# M5_Stick_DCC_Interface_2020-05-23_20-41-.net
KiCad netlist of a schematic drawn in EasyEDA
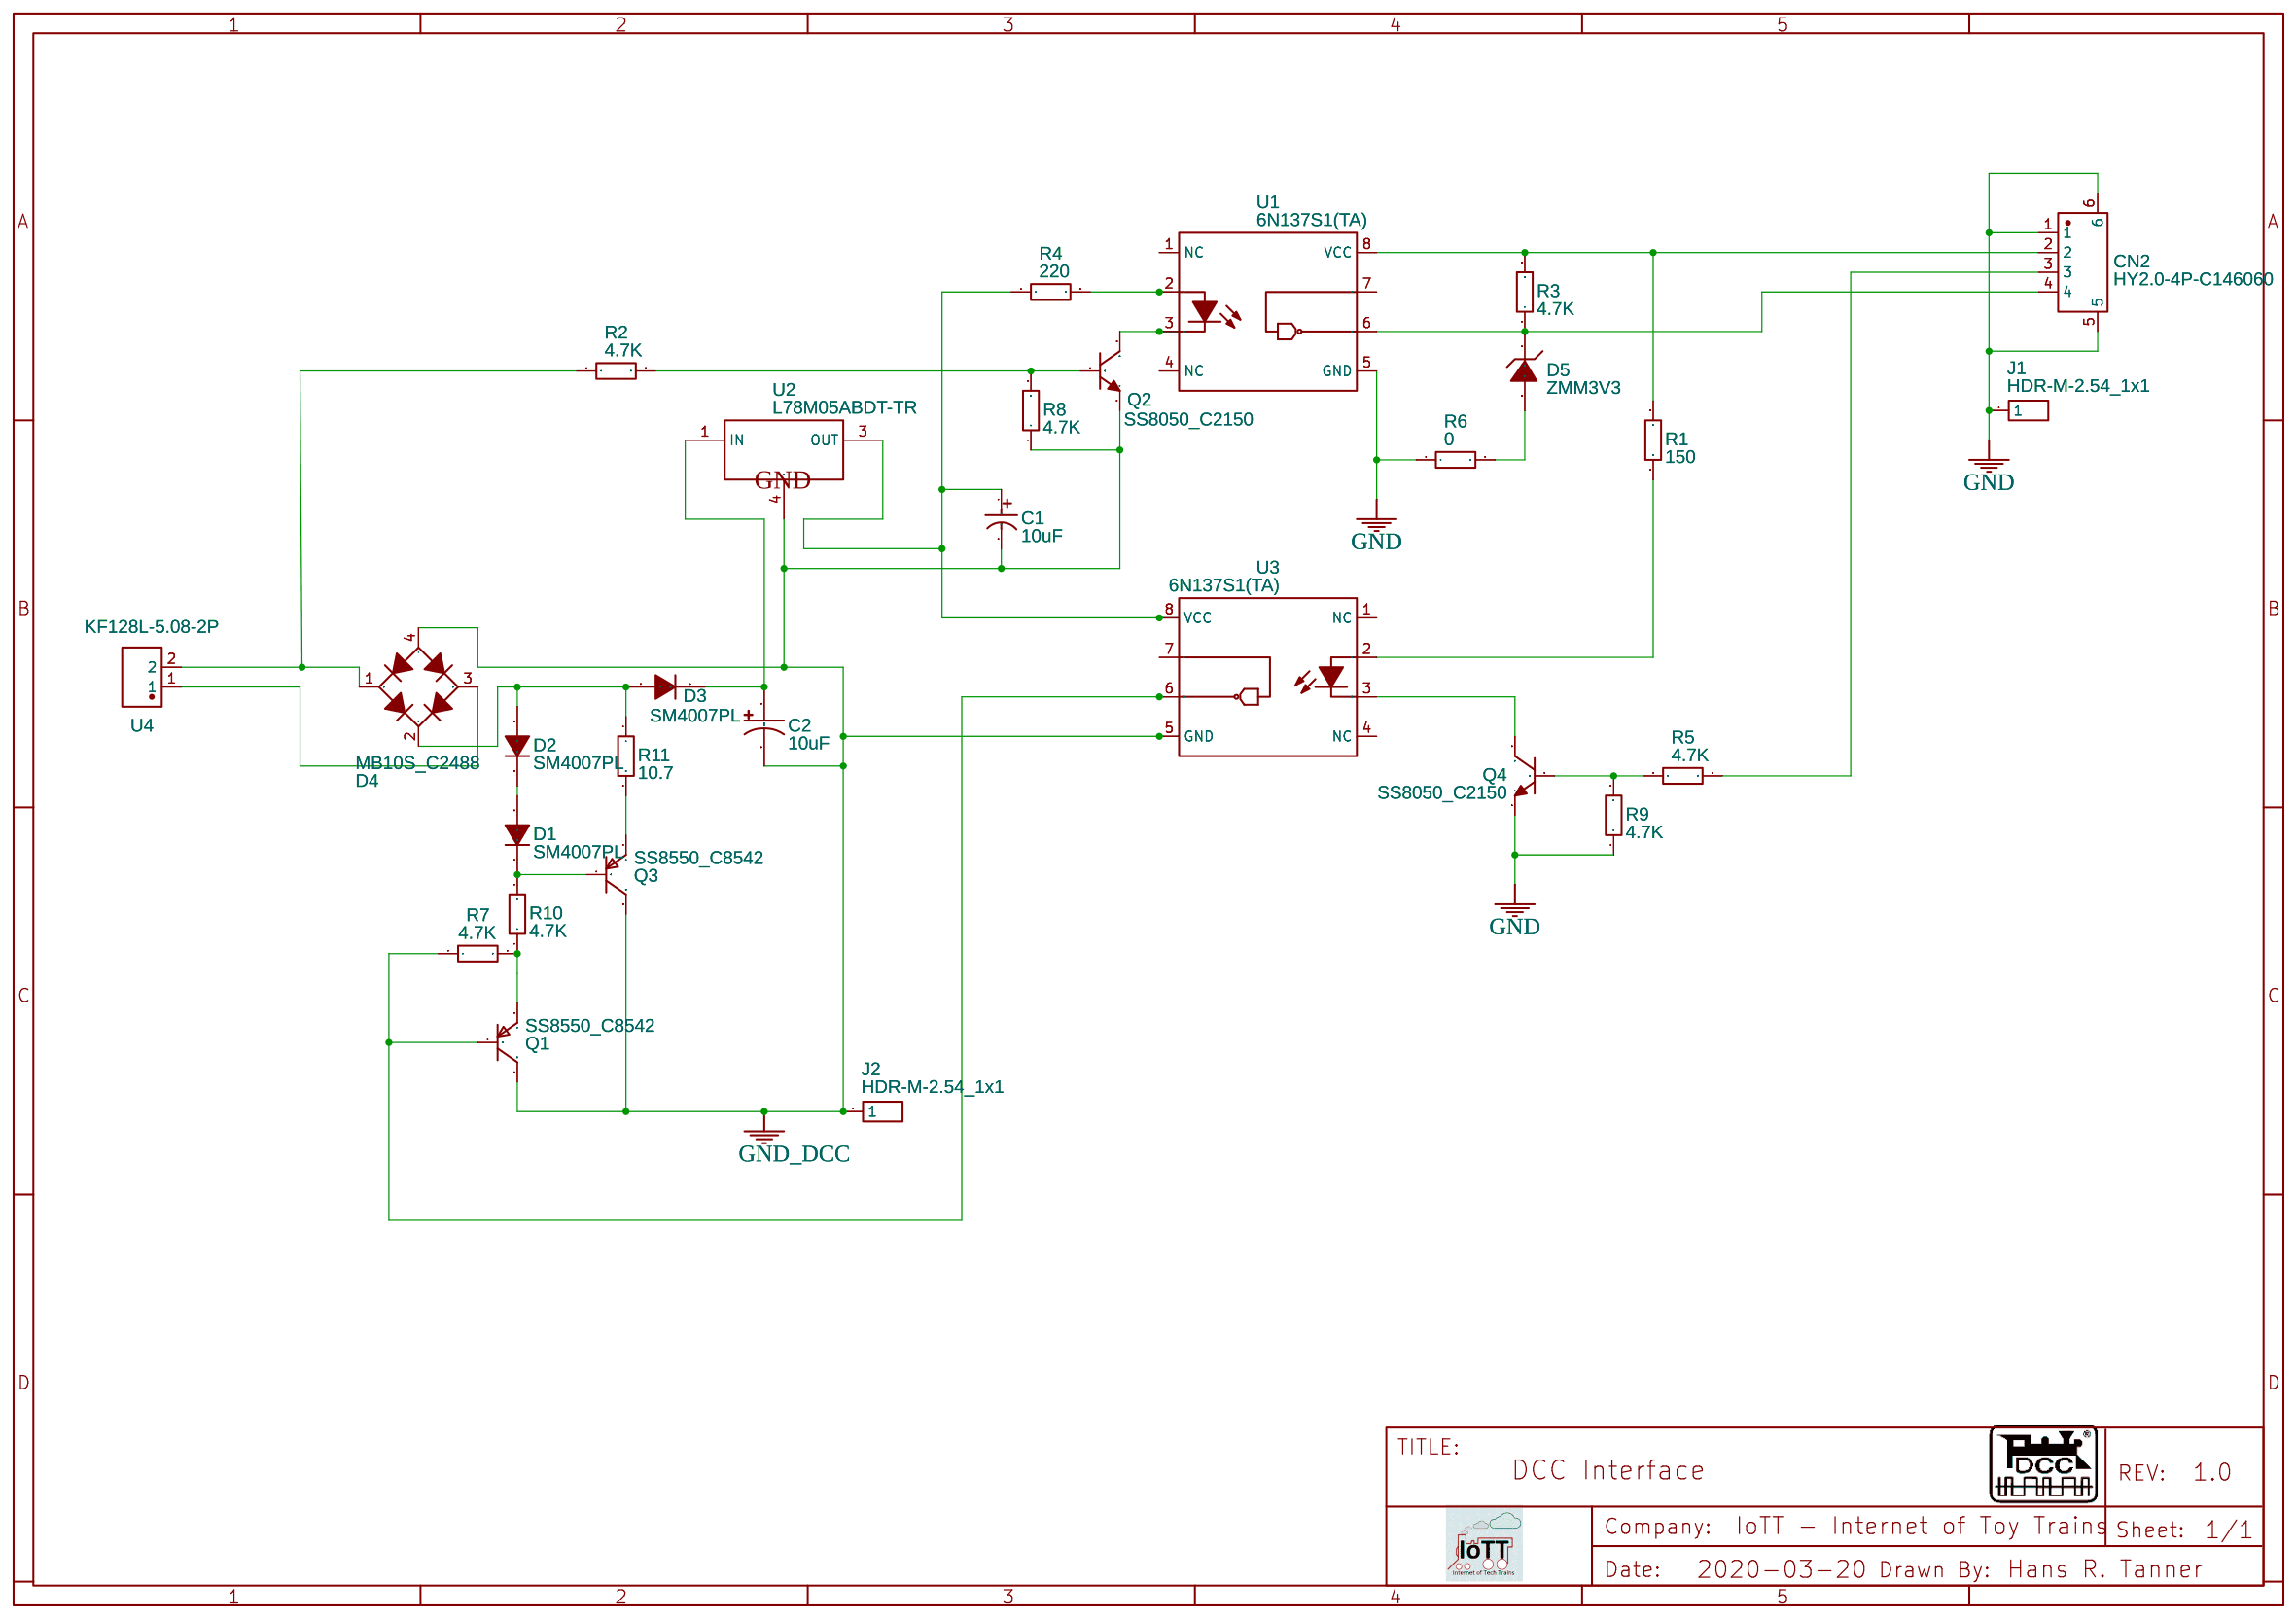
[diagram p0: schematic sheet]

(export (version "E")
  (design (tool "Eeschema 10.0.6"))
  (components
    (comp (ref "C1")
      (value "10uF")
      (fields
        (field (name "BOM_Manufacturer Part") "VE-100M1ETR-0405")
        (field (name "BOM_Supplier Part") "C134721")
      )
      (libsource (lib "") (part "VE-100M1ETR-0405"))
    )
    (comp (ref "C2")
      (value "10uF")
      (fields
        (field (name "BOM_Manufacturer Part") "VE-100M1H0505-TRO")
        (field (name "BOM_Supplier Part") "C249452")
      )
      (libsource (lib "") (part "VE-100M1H0505-TRO"))
    )
    (comp (ref "CN2")
      (value "HY2.0-4P-C146060")
      (fields (field (name "BOM_Supplier Part") "C146060"))
      (libsource (lib "") (part "HY2.0-4P-C146060"))
    )
    (comp (ref "D1")
      (value "SM4007PL")
      (fields (field (name "BOM_Supplier Part") "C64898"))
      (libsource (lib "") (part "SM4007PL"))
    )
    (comp (ref "D2")
      (value "SM4007PL")
      (fields (field (name "BOM_Supplier Part") "C64898"))
      (libsource (lib "") (part "SM4007PL"))
    )
    (comp (ref "D3")
      (value "SM4007PL")
      (fields (field (name "BOM_Supplier Part") "C64898"))
      (libsource (lib "") (part "SM4007PL_1"))
    )
    (comp (ref "D4")
      (value "MB10S_C2488")
      (fields (field (name "BOM_Manufacturer Part") "MB10S") (field (name "BOM_Supplier Part") "C2488"))
      (libsource (lib "") (part "MB10S_C2488"))
    )
    (comp (ref "D5")
      (value "ZMM3V3")
      (fields (field (name "BOM_Supplier Part") "C8056"))
      (libsource (lib "") (part "ZMM3V3"))
    )
    (comp (ref "J1")
      (value "HDR-M-2.54_1x1")
      (fields (field (name "BOM_Supplier Part") "C81276"))
      (libsource (lib "") (part "HDR-M-2.54_1x1"))
    )
    (comp (ref "J2")
      (value "HDR-M-2.54_1x1")
      (fields (field (name "BOM_Supplier Part") "C81276"))
      (libsource (lib "") (part "HDR-M-2.54_1x1"))
    )
    (comp (ref "Q1")
      (value "SS8550_C8542")
      (fields (field (name "BOM_Manufacturer Part") "SS8550") (field (name "BOM_Supplier Part") "C8542"))
      (libsource (lib "") (part "SS8550_C8542"))
    )
    (comp (ref "Q2")
      (value "SS8050_C2150")
      (fields (field (name "BOM_Manufacturer Part") "SS8050") (field (name "BOM_Supplier Part") "C2150"))
      (libsource (lib "") (part "SS8050_C2150"))
    )
    (comp (ref "Q3")
      (value "SS8550_C8542")
      (fields (field (name "BOM_Manufacturer Part") "SS8550") (field (name "BOM_Supplier Part") "C8542"))
      (libsource (lib "") (part "SS8550_C8542"))
    )
    (comp (ref "Q4")
      (value "SS8050_C2150")
      (fields (field (name "BOM_Manufacturer Part") "SS8050") (field (name "BOM_Supplier Part") "C2150"))
      (libsource (lib "") (part "SS8050_C2150_1"))
    )
    (comp (ref "R1")
      (value "150")
      (fields
        (field (name "BOM_Manufacturer Part") "0603WAF1500T5E")
        (field (name "BOM_Supplier Part") "C22808")
      )
      (libsource (lib "") (part "0603WAF1500T5E"))
    )
    (comp (ref "R2")
      (value "4.7K")
      (fields
        (field (name "BOM_Manufacturer Part") "0603WAF4701T5E")
        (field (name "BOM_Supplier Part") "C23162")
      )
      (libsource (lib "") (part "0603WAF4701T5E"))
    )
    (comp (ref "R3")
      (value "4.7K")
      (fields
        (field (name "BOM_Manufacturer Part") "0603WAF4701T5E")
        (field (name "BOM_Supplier Part") "C23162")
      )
      (libsource (lib "") (part "0603WAF1001T5E"))
    )
    (comp (ref "R4")
      (value "220")
      (fields
        (field (name "BOM_Manufacturer Part") "0603WAF2200T5E")
        (field (name "BOM_Supplier Part") "C22962")
      )
      (libsource (lib "") (part "0603WAF1500T5E_1"))
    )
    (comp (ref "R5")
      (value "4.7K")
      (fields
        (field (name "BOM_Manufacturer Part") "0603WAF4701T5E")
        (field (name "BOM_Supplier Part") "C23162")
      )
      (libsource (lib "") (part "0603WAF4701T5E"))
    )
    (comp (ref "R6")
      (value "0")
      (fields
        (field (name "BOM_Manufacturer Part") "0402WGF0000TCE")
        (field (name "BOM_Supplier Part") "C17168")
      )
      (libsource (lib "") (part "0402WGF0000TCE"))
    )
    (comp (ref "R7")
      (value "4.7K")
      (fields
        (field (name "BOM_Manufacturer Part") "0603WAF4701T5E")
        (field (name "BOM_Supplier Part") "C23162")
      )
      (libsource (lib "") (part "0603WAF4701T5E"))
    )
    (comp (ref "R8")
      (value "4.7K")
      (fields
        (field (name "BOM_Manufacturer Part") "0603WAF4701T5E")
        (field (name "BOM_Supplier Part") "C23162")
      )
      (libsource (lib "") (part "0603WAF1001T5E"))
    )
    (comp (ref "R9")
      (value "4.7K")
      (fields
        (field (name "BOM_Manufacturer Part") "0603WAF4701T5E")
        (field (name "BOM_Supplier Part") "C23162")
      )
      (libsource (lib "") (part "0603WAF1001T5E"))
    )
    (comp (ref "R10")
      (value "4.7K")
      (fields
        (field (name "BOM_Manufacturer Part") "0603WAF4701T5E")
        (field (name "BOM_Supplier Part") "C23162")
      )
      (libsource (lib "") (part "0603WAF4701T5E_1"))
    )
    (comp (ref "R11")
      (value "10.7")
      (fields
        (field (name "BOM_Manufacturer Part") "0603WAF107JT5E")
        (field (name "BOM_Supplier Part") "C22774")
      )
      (libsource (lib "") (part "0603WAF107JT5E"))
    )
    (comp (ref "U1")
      (value "6N137S1(TA)")
      (fields (field (name "BOM_Supplier Part") "C110020"))
      (libsource (lib "") (part "6N137S1(TA)_1"))
    )
    (comp (ref "U2")
      (value "L78M05ABDT-TR")
      (fields (field (name "BOM_Supplier Part") "C58069"))
      (libsource (lib "") (part "L78M05ABDT-TR"))
    )
    (comp (ref "U3")
      (value "6N137S1(TA)")
      (fields (field (name "BOM_Supplier Part") "C110020"))
      (libsource (lib "") (part "6N137S1(TA)"))
    )
    (comp (ref "U4")
      (value "KF128L-5.08-2P")
      (fields (field (name "BOM_Supplier Part") "C474940"))
      (libsource (lib "") (part "KF128L-5.08-2P"))
    )
  )
  (nets
    (net (code "1") (name "GND") (class "Default")
      (node (ref "CN2") (pin "1") (pinfunction "1_1") (pintype "unspecified"))
      (node (ref "CN2") (pin "5") (pinfunction "5_5") (pintype "unspecified"))
      (node (ref "CN2") (pin "6") (pinfunction "6_6") (pintype "unspecified"))
      (node (ref "J1") (pin "1") (pinfunction "1_1") (pintype "input"))
      (node (ref "Q4") (pin "2") (pinfunction "E_2") (pintype "unspecified"))
      (node (ref "R6") (pin "1") (pinfunction "1_1") (pintype "input"))
      (node (ref "R9") (pin "1") (pinfunction "1_1") (pintype "input"))
      (node (ref "U1") (pin "5") (pinfunction "GND_5") (pintype "unspecified"))
    )
    (net (code "2") (name "GND_DCC") (class "Default")
      (node (ref "C1") (pin "2") (pinfunction "2_2") (pintype "input"))
      (node (ref "C2") (pin "2") (pinfunction "2_2") (pintype "unspecified"))
      (node (ref "D4") (pin "4") (pinfunction "-_4") (pintype "unspecified"))
      (node (ref "J2") (pin "1") (pinfunction "1_1") (pintype "input"))
      (node (ref "Q1") (pin "3") (pinfunction "C_3") (pintype "unspecified"))
      (node (ref "Q2") (pin "2") (pinfunction "E_2") (pintype "unspecified"))
      (node (ref "Q3") (pin "3") (pinfunction "C_3") (pintype "unspecified"))
      (node (ref "R8") (pin "1") (pinfunction "1_1") (pintype "input"))
      (node (ref "U2") (pin "4") (pinfunction "GND_4") (pintype "passive"))
      (node (ref "U3") (pin "5") (pinfunction "GND_5") (pintype "unspecified"))
    )
    (net (code "3") (name "Net-(CN2-Pad3)") (class "Default")
      (node (ref "CN2") (pin "3") (pinfunction "3_3") (pintype "unspecified"))
      (node (ref "R5") (pin "2") (pinfunction "2_2") (pintype "input"))
    )
    (net (code "4") (name "Net-(D1-A)") (class "Default")
      (node (ref "D1") (pin "2") (pinfunction "A_2") (pintype "unspecified"))
      (node (ref "D2") (pin "1") (pinfunction "C_1") (pintype "unspecified"))
    )
    (net (code "5") (name "Net-(D1-C)") (class "Default")
      (node (ref "D1") (pin "1") (pinfunction "C_1") (pintype "unspecified"))
      (node (ref "Q3") (pin "1") (pinfunction "B_1") (pintype "unspecified"))
      (node (ref "R10") (pin "2") (pinfunction "2_2") (pintype "input"))
    )
    (net (code "6") (name "Net-(D2-A)") (class "Default")
      (node (ref "D2") (pin "2") (pinfunction "A_2") (pintype "unspecified"))
      (node (ref "D3") (pin "2") (pinfunction "A_2") (pintype "unspecified"))
      (node (ref "D4") (pin "2") (pinfunction "+_2") (pintype "unspecified"))
      (node (ref "R11") (pin "1") (pinfunction "1_1") (pintype "input"))
    )
    (net (code "7") (name "Net-(D3-C)") (class "Default")
      (node (ref "C2") (pin "1") (pinfunction "1_1") (pintype "unspecified"))
      (node (ref "D3") (pin "1") (pinfunction "C_1") (pintype "unspecified"))
      (node (ref "U2") (pin "1") (pinfunction "IN_1") (pintype "passive"))
    )
    (net (code "8") (name "Net-(D4-C1)") (class "Default")
      (node (ref "D4") (pin "1") (pinfunction "C1_1") (pintype "unspecified"))
      (node (ref "R2") (pin "1") (pinfunction "1_1") (pintype "input"))
      (node (ref "U4") (pin "2") (pinfunction "2_2") (pintype "unspecified"))
    )
    (net (code "9") (name "Net-(D4-C2)") (class "Default")
      (node (ref "D4") (pin "3") (pinfunction "C2_3") (pintype "unspecified"))
      (node (ref "U4") (pin "1") (pinfunction "1_1") (pintype "unspecified"))
    )
    (net (code "10") (name "Net-(D5-A)") (class "Default")
      (node (ref "D5") (pin "2") (pinfunction "A_2") (pintype "unspecified"))
      (node (ref "R6") (pin "2") (pinfunction "2_2") (pintype "input"))
    )
    (net (code "11") (name "Net-(D5-C)") (class "Default")
      (node (ref "CN2") (pin "4") (pinfunction "4_4") (pintype "unspecified"))
      (node (ref "D5") (pin "1") (pinfunction "C_1") (pintype "unspecified"))
      (node (ref "R3") (pin "1") (pinfunction "1_1") (pintype "input"))
      (node (ref "U1") (pin "6") (pinfunction "VOUT_6") (pintype "unspecified"))
    )
    (net (code "12") (name "Net-(Q1-B)") (class "Default")
      (node (ref "Q1") (pin "1") (pinfunction "B_1") (pintype "unspecified"))
      (node (ref "R7") (pin "1") (pinfunction "1_1") (pintype "input"))
      (node (ref "U3") (pin "6") (pinfunction "VOUT_6") (pintype "unspecified"))
    )
    (net (code "13") (name "Net-(Q1-E)") (class "Default")
      (node (ref "Q1") (pin "2") (pinfunction "E_2") (pintype "unspecified"))
      (node (ref "R10") (pin "1") (pinfunction "1_1") (pintype "input"))
      (node (ref "R7") (pin "2") (pinfunction "2_2") (pintype "input"))
    )
    (net (code "14") (name "Net-(Q2-B)") (class "Default")
      (node (ref "Q2") (pin "1") (pinfunction "B_1") (pintype "unspecified"))
      (node (ref "R2") (pin "2") (pinfunction "2_2") (pintype "input"))
      (node (ref "R8") (pin "2") (pinfunction "2_2") (pintype "input"))
    )
    (net (code "15") (name "Net-(Q2-C)") (class "Default")
      (node (ref "Q2") (pin "3") (pinfunction "C_3") (pintype "unspecified"))
      (node (ref "U1") (pin "3") (pinfunction "CAT_3") (pintype "unspecified"))
    )
    (net (code "16") (name "Net-(Q3-E)") (class "Default")
      (node (ref "Q3") (pin "2") (pinfunction "E_2") (pintype "unspecified"))
      (node (ref "R11") (pin "2") (pinfunction "2_2") (pintype "input"))
    )
    (net (code "17") (name "Net-(Q4-B)") (class "Default")
      (node (ref "Q4") (pin "1") (pinfunction "B_1") (pintype "unspecified"))
      (node (ref "R5") (pin "1") (pinfunction "1_1") (pintype "input"))
      (node (ref "R9") (pin "2") (pinfunction "2_2") (pintype "input"))
    )
    (net (code "18") (name "Net-(Q4-C)") (class "Default")
      (node (ref "Q4") (pin "3") (pinfunction "C_3") (pintype "unspecified"))
      (node (ref "U3") (pin "3") (pinfunction "CAT_3") (pintype "unspecified"))
    )
    (net (code "19") (name "Net-(U1-AN)") (class "Default")
      (node (ref "R4") (pin "2") (pinfunction "2_2") (pintype "input"))
      (node (ref "U1") (pin "2") (pinfunction "AN_2") (pintype "unspecified"))
    )
    (net (code "20") (name "Net-(U1-VCC)") (class "Default")
      (node (ref "CN2") (pin "2") (pinfunction "2_2") (pintype "unspecified"))
      (node (ref "R1") (pin "2") (pinfunction "2_2") (pintype "input"))
      (node (ref "R3") (pin "2") (pinfunction "2_2") (pintype "input"))
      (node (ref "U1") (pin "8") (pinfunction "VCC_8") (pintype "unspecified"))
    )
    (net (code "21") (name "Net-(U2-OUT)") (class "Default")
      (node (ref "C1") (pin "1") (pinfunction "1_1") (pintype "input"))
      (node (ref "R4") (pin "1") (pinfunction "1_1") (pintype "input"))
      (node (ref "U2") (pin "3") (pinfunction "OUT_3") (pintype "passive"))
      (node (ref "U3") (pin "8") (pinfunction "VCC_8") (pintype "unspecified"))
    )
    (net (code "22") (name "Net-(U3-AN)") (class "Default")
      (node (ref "R1") (pin "1") (pinfunction "1_1") (pintype "input"))
      (node (ref "U3") (pin "2") (pinfunction "AN_2") (pintype "unspecified"))
    )
    (net (code "23") (name "unconnected-(U1-NC-Pad1)") (class "Default")
      (node (ref "U1") (pin "1") (pinfunction "NC_1") (pintype "unspecified"))
    )
    (net (code "24") (name "unconnected-(U1-NC-Pad4)") (class "Default")
      (node (ref "U1") (pin "4") (pinfunction "NC_4") (pintype "unspecified"))
    )
    (net (code "25") (name "unconnected-(U1-VE-Pad7)") (class "Default")
      (node (ref "U1") (pin "7") (pinfunction "VE_7") (pintype "unspecified"))
    )
    (net (code "26") (name "unconnected-(U3-NC-Pad1)") (class "Default")
      (node (ref "U3") (pin "1") (pinfunction "NC_1") (pintype "unspecified"))
    )
    (net (code "27") (name "unconnected-(U3-NC-Pad4)") (class "Default")
      (node (ref "U3") (pin "4") (pinfunction "NC_4") (pintype "unspecified"))
    )
    (net (code "28") (name "unconnected-(U3-VE-Pad7)") (class "Default")
      (node (ref "U3") (pin "7") (pinfunction "VE_7") (pintype "unspecified"))
    )
  )
)
